# CSX_Capsense.net
KiCad netlist of a schematic drawn in Altium Designer
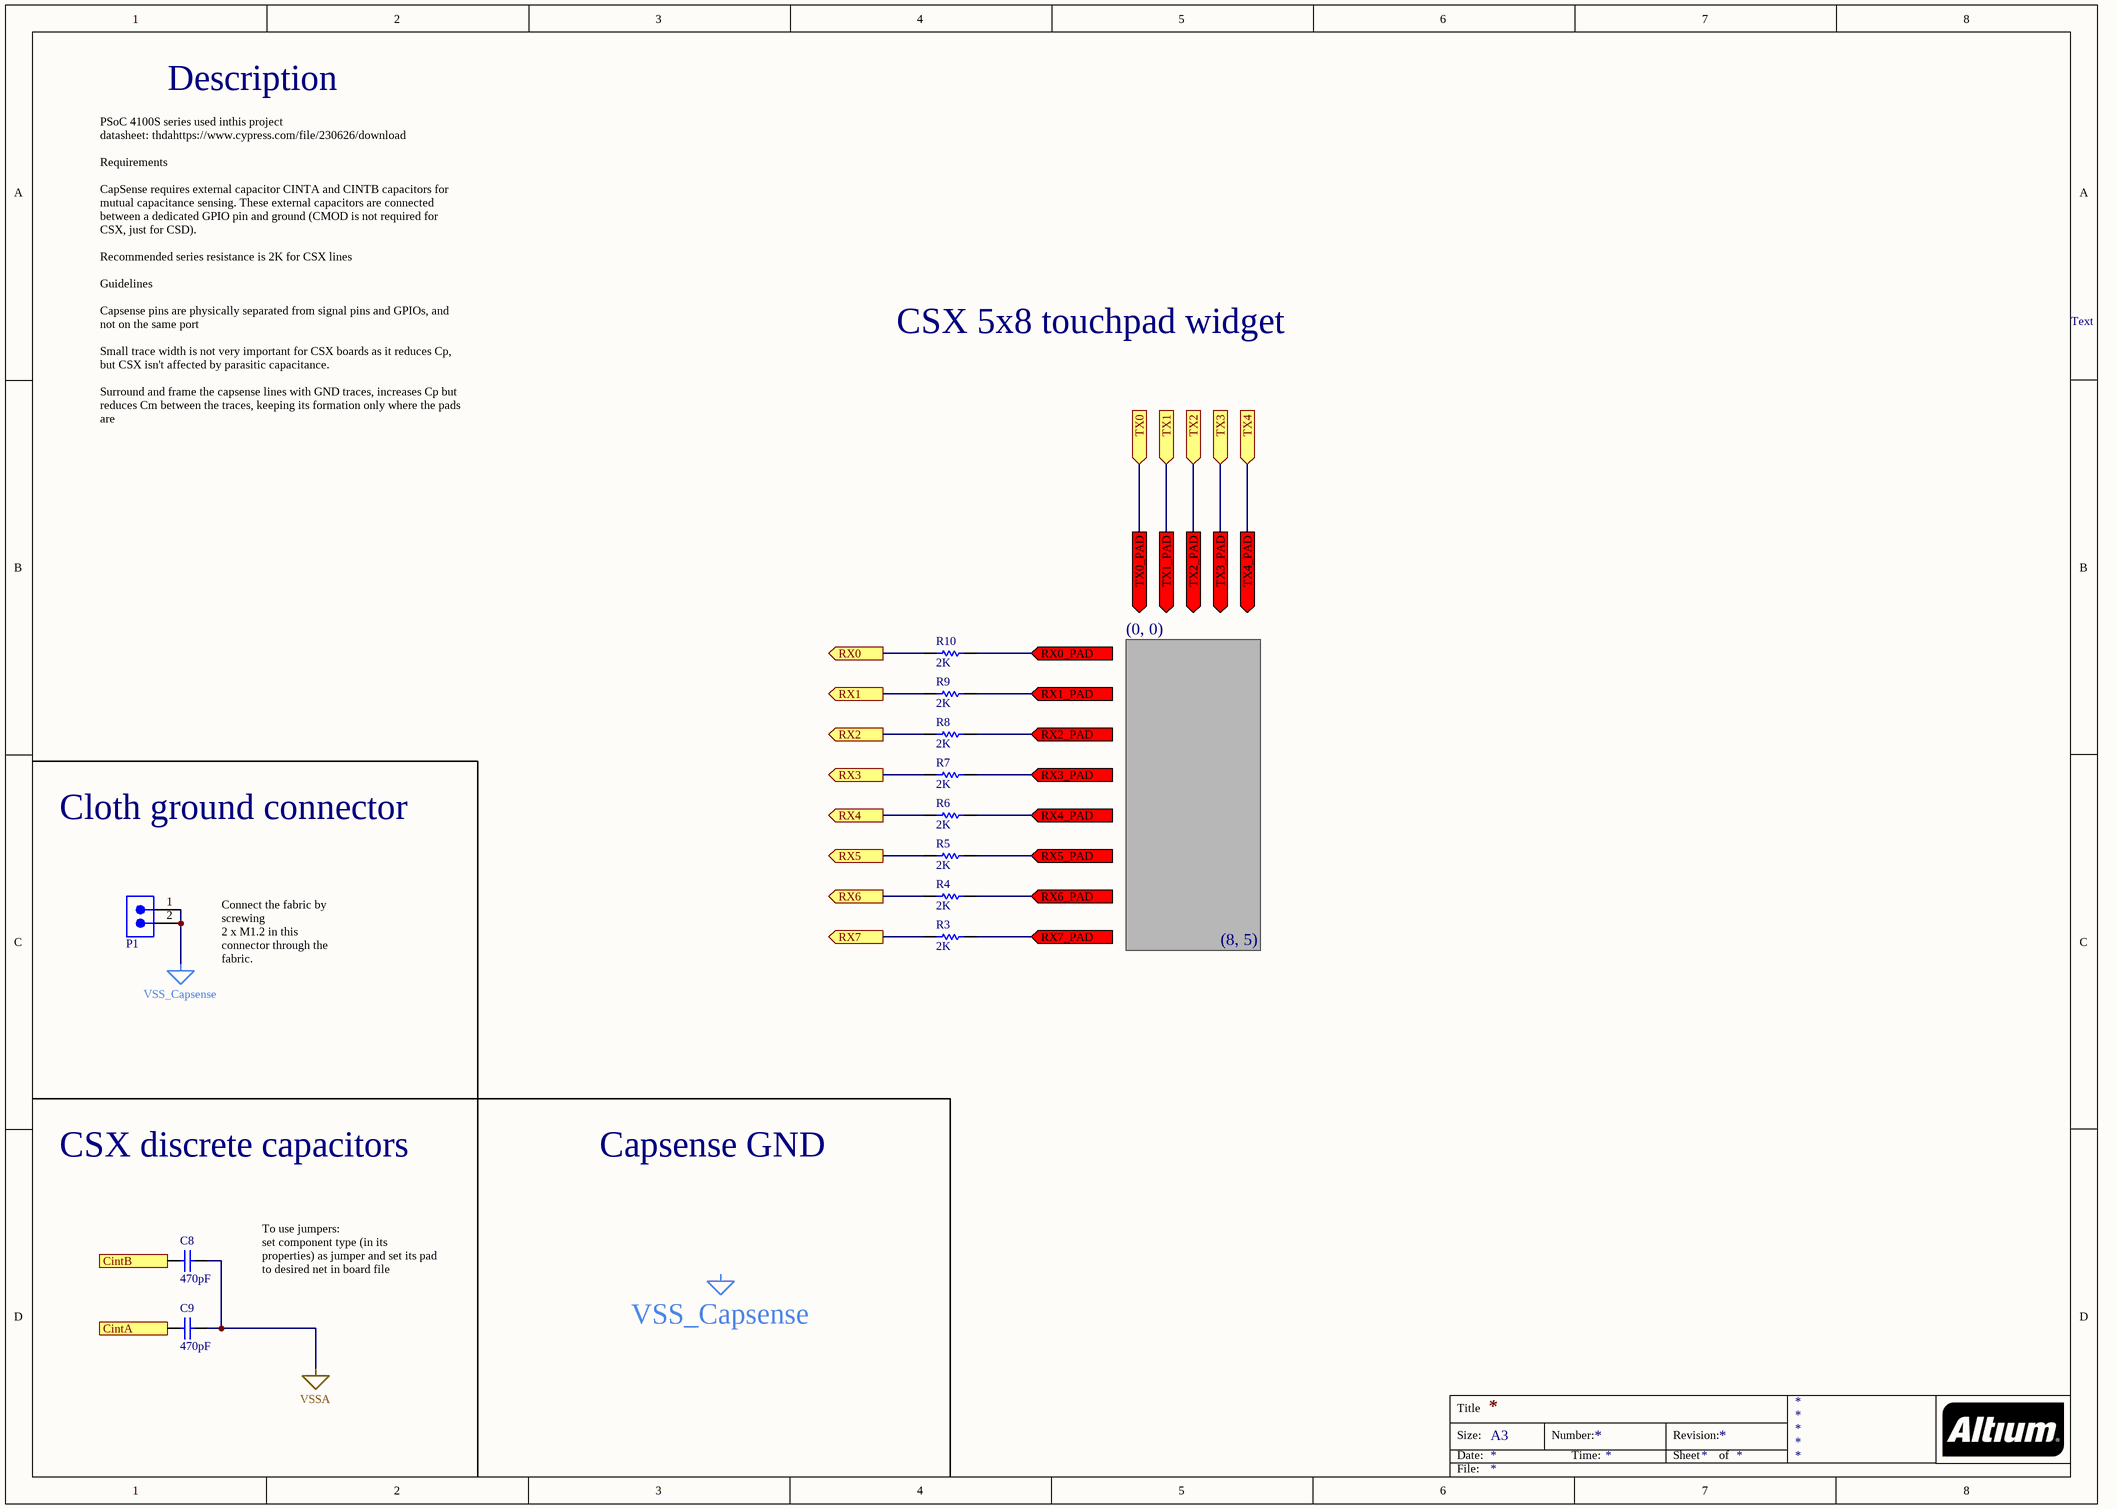
[diagram p0: CSX_Capsense.SchDoc]

(export (version "E")
  (design (tool "Eeschema 10.0.6"))
  (components
    (comp (ref "C8")
      (value "470pF")
      (footprint "CAPC0603(1608)100_N")
      (description "CAP 470pF 10V ±10% 0603 (1608 Metric) Thickness 1mm SMD")
      (fields (field (name "TOLERANCE") "Â±10%"))
      (libsource (lib "Altium Content Vault") (part "CAP"))
    )
    (comp (ref "C9")
      (value "470pF")
      (footprint "CAPC0603(1608)100_N")
      (description "CAP 470pF 10V ±10% 0603 (1608 Metric) Thickness 1mm SMD")
      (fields (field (name "TOLERANCE") "Â±10%"))
      (libsource (lib "Altium Content Vault") (part "CAP"))
    )
    (comp (ref "P1")
      (value "MTLW-102-05-T-S-172")
      (footprint "SMTC-MTLW-102-05-X-S-172")
      (fields (field (name "MANUFACTURER") "Samtec"))
      (libsource (lib "Altium Content Vault") (part "SMTC-MTLW-102-05-X-S-172"))
    )
    (comp (ref "R3")
      (value "2K")
      (footprint "RESC0603(1608)_N")
      (description "2K 0.1W 5% 0603 (1608 Metric)  SMD")
      (fields (field (name "TOLERANCE") "5 %") (field (name "POWER") "0.1 W"))
      (libsource (lib "Altium Content Vault") (part "RES"))
    )
    (comp (ref "R4")
      (value "2K")
      (footprint "RESC0603(1608)_N")
      (description "2K 0.1W 5% 0603 (1608 Metric)  SMD")
      (fields (field (name "TOLERANCE") "5 %") (field (name "POWER") "0.1 W"))
      (libsource (lib "Altium Content Vault") (part "RES"))
    )
    (comp (ref "R5")
      (value "2K")
      (footprint "RESC0603(1608)_N")
      (description "2K 0.1W 5% 0603 (1608 Metric)  SMD")
      (fields (field (name "TOLERANCE") "5 %") (field (name "POWER") "0.1 W"))
      (libsource (lib "Altium Content Vault") (part "RES"))
    )
    (comp (ref "R6")
      (value "2K")
      (footprint "RESC0603(1608)_N")
      (description "2K 0.1W 5% 0603 (1608 Metric)  SMD")
      (fields (field (name "TOLERANCE") "5 %") (field (name "POWER") "0.1 W"))
      (libsource (lib "Altium Content Vault") (part "RES"))
    )
    (comp (ref "R7")
      (value "2K")
      (footprint "RESC0603(1608)_N")
      (description "2K 0.1W 5% 0603 (1608 Metric)  SMD")
      (fields (field (name "TOLERANCE") "5 %") (field (name "POWER") "0.1 W"))
      (libsource (lib "Altium Content Vault") (part "RES"))
    )
    (comp (ref "R8")
      (value "2K")
      (footprint "RESC0603(1608)_N")
      (description "2K 0.1W 5% 0603 (1608 Metric)  SMD")
      (fields (field (name "TOLERANCE") "5 %") (field (name "POWER") "0.1 W"))
      (libsource (lib "Altium Content Vault") (part "RES"))
    )
    (comp (ref "R9")
      (value "2K")
      (footprint "RESC0603(1608)_N")
      (description "2K 0.1W 5% 0603 (1608 Metric)  SMD")
      (fields (field (name "TOLERANCE") "5 %") (field (name "POWER") "0.1 W"))
      (libsource (lib "Altium Content Vault") (part "RES"))
    )
    (comp (ref "R10")
      (value "2K")
      (footprint "RESC0603(1608)_N")
      (description "2K 0.1W 5% 0603 (1608 Metric)  SMD")
      (fields (field (name "TOLERANCE") "5 %") (field (name "POWER") "0.1 W"))
      (libsource (lib "Altium Content Vault") (part "RES"))
    )
  )
  (nets
    (net (code "1") (name "/CintA") (class "Default")
      (node (ref "C9") (pin "1") (pinfunction "1_1") (pintype "passive"))
    )
    (net (code "2") (name "/CintB") (class "Default")
      (node (ref "C8") (pin "1") (pinfunction "1_1") (pintype "passive"))
    )
    (net (code "3") (name "/RX0") (class "Default")
      (node (ref "R10") (pin "1") (pinfunction "1_1") (pintype "passive"))
    )
    (net (code "4") (name "/RX0_PAD") (class "Default")
      (node (ref "R10") (pin "2") (pinfunction "2_2") (pintype "passive"))
    )
    (net (code "5") (name "/RX1") (class "Default")
      (node (ref "R9") (pin "1") (pinfunction "1_1") (pintype "passive"))
    )
    (net (code "6") (name "/RX1_PAD") (class "Default")
      (node (ref "R9") (pin "2") (pinfunction "2_2") (pintype "passive"))
    )
    (net (code "7") (name "/RX2") (class "Default")
      (node (ref "R8") (pin "1") (pinfunction "1_1") (pintype "passive"))
    )
    (net (code "8") (name "/RX2_PAD") (class "Default")
      (node (ref "R8") (pin "2") (pinfunction "2_2") (pintype "passive"))
    )
    (net (code "9") (name "/RX3") (class "Default")
      (node (ref "R7") (pin "1") (pinfunction "1_1") (pintype "passive"))
    )
    (net (code "10") (name "/RX3_PAD") (class "Default")
      (node (ref "R7") (pin "2") (pinfunction "2_2") (pintype "passive"))
    )
    (net (code "11") (name "/RX4") (class "Default")
      (node (ref "R6") (pin "1") (pinfunction "1_1") (pintype "passive"))
    )
    (net (code "12") (name "/RX4_PAD") (class "Default")
      (node (ref "R6") (pin "2") (pinfunction "2_2") (pintype "passive"))
    )
    (net (code "13") (name "/RX5") (class "Default")
      (node (ref "R5") (pin "1") (pinfunction "1_1") (pintype "passive"))
    )
    (net (code "14") (name "/RX5_PAD") (class "Default")
      (node (ref "R5") (pin "2") (pinfunction "2_2") (pintype "passive"))
    )
    (net (code "15") (name "/RX6") (class "Default")
      (node (ref "R4") (pin "1") (pinfunction "1_1") (pintype "passive"))
    )
    (net (code "16") (name "/RX6_PAD") (class "Default")
      (node (ref "R4") (pin "2") (pinfunction "2_2") (pintype "passive"))
    )
    (net (code "17") (name "/RX7") (class "Default")
      (node (ref "R3") (pin "1") (pinfunction "1_1") (pintype "passive"))
    )
    (net (code "18") (name "/RX7_PAD") (class "Default")
      (node (ref "R3") (pin "2") (pinfunction "2_2") (pintype "passive"))
    )
    (net (code "24") (name "VSSA") (class "Default")
      (node (ref "C8") (pin "2") (pinfunction "2_2") (pintype "passive"))
      (node (ref "C9") (pin "2") (pinfunction "2_2") (pintype "passive"))
    )
    (net (code "25") (name "VSS_Capsense") (class "Default")
      (node (ref "P1") (pin "1") (pinfunction "1_1") (pintype "passive"))
      (node (ref "P1") (pin "2") (pinfunction "2_2") (pintype "passive"))
    )
  )
)
